# stepperDriver.net
KiCad netlist of a schematic drawn in EAGLE
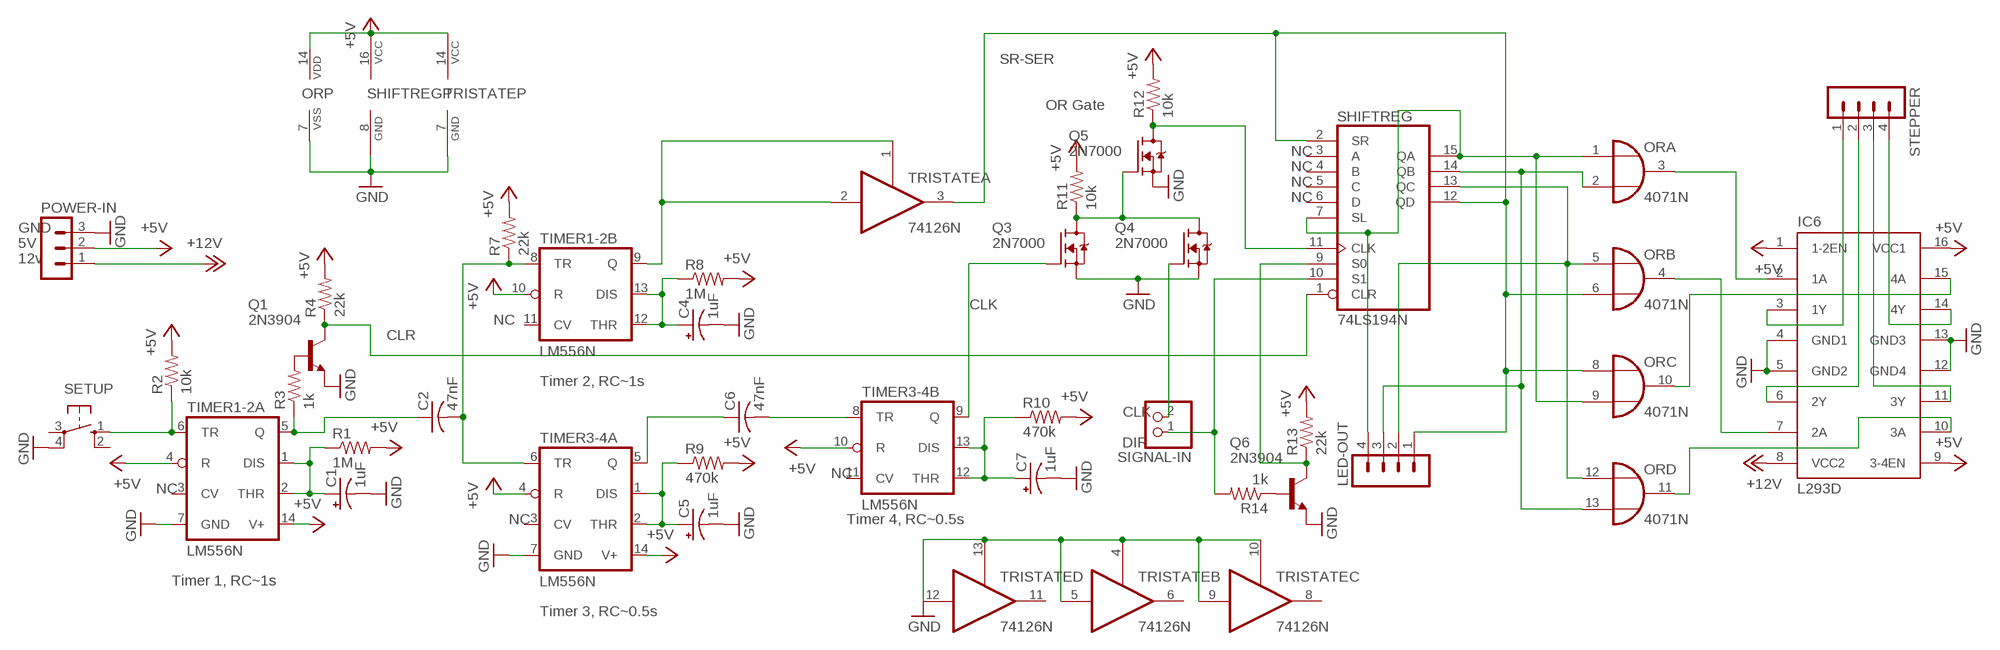
[diagram p0: schematic, sheet 1]

(export (version "E")
  (design (tool "Eeschema 10.0.6"))
  (components
    (comp (ref "C1")
      (value "1uF")
      (footprint "eagle-import:E2,5-6")
      (libsource (lib "eagle-import") (part "CPOL-USE2.5-6"))
    )
    (comp (ref "C2")
      (value "47nF")
      (footprint "eagle-import:C025-025X050")
      (libsource (lib "eagle-import") (part "C-US025-025X050"))
    )
    (comp (ref "C4")
      (value "1uF")
      (footprint "eagle-import:E2,5-6")
      (libsource (lib "eagle-import") (part "CPOL-USE2.5-6"))
    )
    (comp (ref "C5")
      (value "1uF")
      (footprint "eagle-import:E2,5-6")
      (libsource (lib "eagle-import") (part "CPOL-USE2.5-6"))
    )
    (comp (ref "C6")
      (value "47nF")
      (footprint "eagle-import:C025-025X050")
      (libsource (lib "eagle-import") (part "C-US025-025X050"))
    )
    (comp (ref "C7")
      (value "1uF")
      (footprint "eagle-import:E2,5-6")
      (libsource (lib "eagle-import") (part "CPOL-USE2.5-6"))
    )
    (comp (ref "IC6")
      (value "L293D")
      (footprint "eagle-import:DIL16")
      (libsource (lib "eagle-import") (part "L293D"))
    )
    (comp (ref "LED-OUT")
      (value "MA04-1")
      (footprint "eagle-import:MA04-1")
      (libsource (lib "eagle-import") (part "MA04-1"))
    )
    (comp (ref "OR")
      (value "4071N")
      (footprint "eagle-import:DIL14")
      (libsource (lib "eagle-import") (part "4071N"))
    )
    (comp (ref "POWER-IN")
      (value "MA03-1")
      (footprint "eagle-import:MA03-1")
      (libsource (lib "eagle-import") (part "MA03-1"))
    )
    (comp (ref "Q1")
      (value "2N3904")
      (footprint "eagle-import:TO92")
      (libsource (lib "eagle-import") (part "2N3904"))
    )
    (comp (ref "Q3")
      (value "2N7000")
      (footprint "eagle-import:TO92-")
      (libsource (lib "eagle-import") (part "2N7000"))
    )
    (comp (ref "Q4")
      (value "2N7000")
      (footprint "eagle-import:TO92-")
      (libsource (lib "eagle-import") (part "2N7000"))
    )
    (comp (ref "Q5")
      (value "2N7000")
      (footprint "eagle-import:TO92-")
      (libsource (lib "eagle-import") (part "2N7000"))
    )
    (comp (ref "Q6")
      (value "2N3904")
      (footprint "eagle-import:TO92")
      (libsource (lib "eagle-import") (part "2N3904"))
    )
    (comp (ref "R1")
      (value "1M")
      (footprint "eagle-import:0204_7")
      (libsource (lib "eagle-import") (part "R-US_0204/7"))
    )
    (comp (ref "R2")
      (value "10k")
      (footprint "eagle-import:0204_7")
      (libsource (lib "eagle-import") (part "R-US_0204/7"))
    )
    (comp (ref "R3")
      (value "1k")
      (footprint "eagle-import:0204_7")
      (libsource (lib "eagle-import") (part "R-US_0204/7"))
    )
    (comp (ref "R4")
      (value "22k")
      (footprint "eagle-import:0204_7")
      (libsource (lib "eagle-import") (part "R-US_0204/7"))
    )
    (comp (ref "R7")
      (value "22k")
      (footprint "eagle-import:0204_7")
      (libsource (lib "eagle-import") (part "R-US_0204/7"))
    )
    (comp (ref "R8")
      (value "1M")
      (footprint "eagle-import:0204_7")
      (libsource (lib "eagle-import") (part "R-US_0204/7"))
    )
    (comp (ref "R9")
      (value "470k")
      (footprint "eagle-import:0204_7")
      (libsource (lib "eagle-import") (part "R-US_0204/7"))
    )
    (comp (ref "R10")
      (value "470k")
      (footprint "eagle-import:0204_7")
      (libsource (lib "eagle-import") (part "R-US_0204/7"))
    )
    (comp (ref "R11")
      (value "10k")
      (footprint "eagle-import:0204_7")
      (libsource (lib "eagle-import") (part "R-US_0204/7"))
    )
    (comp (ref "R12")
      (value "10k")
      (footprint "eagle-import:0204_7")
      (libsource (lib "eagle-import") (part "R-US_0204/7"))
    )
    (comp (ref "R13")
      (value "22k")
      (footprint "eagle-import:0204_7")
      (libsource (lib "eagle-import") (part "R-US_0204/7"))
    )
    (comp (ref "R14")
      (value "1k")
      (footprint "eagle-import:0204_7")
      (libsource (lib "eagle-import") (part "R-US_0204/7"))
    )
    (comp (ref "SETUP")
      (value "10-XX")
      (footprint "eagle-import:B3F-10XX")
      (fields (field (name "MPN") "B3F-1000"))
      (libsource (lib "eagle-import") (part "10-XX"))
    )
    (comp (ref "SHIFTREG")
      (value "74LS194N")
      (footprint "eagle-import:DIL16")
      (libsource (lib "eagle-import") (part "74194NLS"))
    )
    (comp (ref "SIGNAL-IN")
      (value "PINHD-1X2")
      (footprint "eagle-import:1X02")
      (libsource (lib "eagle-import") (part "PINHD-1X2"))
    )
    (comp (ref "STEPPER")
      (value "MA04-1")
      (footprint "eagle-import:MA04-1")
      (libsource (lib "eagle-import") (part "MA04-1"))
    )
    (comp (ref "TIMER1-2")
      (value "LM556N")
      (footprint "eagle-import:DIL14")
      (libsource (lib "eagle-import") (part "556NLM"))
    )
    (comp (ref "TIMER3-4")
      (value "LM556N")
      (footprint "eagle-import:DIL14")
      (libsource (lib "eagle-import") (part "556NLM"))
    )
    (comp (ref "TRISTATE")
      (value "74126N")
      (footprint "eagle-import:DIL14")
      (libsource (lib "eagle-import") (part "74126N"))
    )
  )
  (nets
    (net (code "1") (name "+5V") (class "Default")
      (node (ref "IC6") (pin "1") (pinfunction "1-2EN_1") (pintype "input"))
      (node (ref "IC6") (pin "16") (pinfunction "VCC1_16") (pintype "power_in"))
      (node (ref "IC6") (pin "9") (pinfunction "3-4EN_9") (pintype "input"))
      (node (ref "OR") (pin "14") (pinfunction "VDD_14") (pintype "power_in"))
      (node (ref "POWER-IN") (pin "2") (pinfunction "2_2") (pintype "passive"))
      (node (ref "R1") (pin "2") (pinfunction "2_2") (pintype "passive"))
      (node (ref "R10") (pin "2") (pinfunction "2_2") (pintype "passive"))
      (node (ref "R11") (pin "2") (pinfunction "2_2") (pintype "passive"))
      (node (ref "R12") (pin "2") (pinfunction "2_2") (pintype "passive"))
      (node (ref "R13") (pin "2") (pinfunction "2_2") (pintype "passive"))
      (node (ref "R2") (pin "2") (pinfunction "2_2") (pintype "passive"))
      (node (ref "R4") (pin "2") (pinfunction "2_2") (pintype "passive"))
      (node (ref "R7") (pin "2") (pinfunction "2_2") (pintype "passive"))
      (node (ref "R8") (pin "2") (pinfunction "2_2") (pintype "passive"))
      (node (ref "R9") (pin "2") (pinfunction "2_2") (pintype "passive"))
      (node (ref "SHIFTREG") (pin "16") (pinfunction "VCC_16") (pintype "power_in"))
      (node (ref "TIMER1-2") (pin "10") (pinfunction "R_10") (pintype "input"))
      (node (ref "TIMER1-2") (pin "14") (pinfunction "V+_14") (pintype "power_in"))
      (node (ref "TIMER1-2") (pin "4") (pinfunction "R_4") (pintype "input"))
      (node (ref "TIMER3-4") (pin "10") (pinfunction "R_10") (pintype "input"))
      (node (ref "TIMER3-4") (pin "14") (pinfunction "V+_14") (pintype "power_in"))
      (node (ref "TIMER3-4") (pin "4") (pinfunction "R_4") (pintype "input"))
      (node (ref "TRISTATE") (pin "14") (pinfunction "VCC_14") (pintype "power_in"))
    )
    (net (code "2") (name "+12V") (class "Default")
      (node (ref "IC6") (pin "8") (pinfunction "VCC2_8") (pintype "power_in"))
      (node (ref "POWER-IN") (pin "1") (pinfunction "1_1") (pintype "passive"))
    )
    (net (code "3") (name "GND") (class "Default")
      (node (ref "C1") (pin "-") (pinfunction "-_-") (pintype "passive"))
      (node (ref "C4") (pin "-") (pinfunction "-_-") (pintype "passive"))
      (node (ref "C5") (pin "-") (pinfunction "-_-") (pintype "passive"))
      (node (ref "C7") (pin "-") (pinfunction "-_-") (pintype "passive"))
      (node (ref "IC6") (pin "12") (pinfunction "GND4_12") (pintype "power_in"))
      (node (ref "IC6") (pin "13") (pinfunction "GND3_13") (pintype "power_in"))
      (node (ref "IC6") (pin "4") (pinfunction "GND1_4") (pintype "power_in"))
      (node (ref "IC6") (pin "5") (pinfunction "GND2_5") (pintype "power_in"))
      (node (ref "OR") (pin "7") (pinfunction "VSS_7") (pintype "power_in"))
      (node (ref "POWER-IN") (pin "3") (pinfunction "3_3") (pintype "passive"))
      (node (ref "Q1") (pin "3") (pinfunction "E_3") (pintype "passive"))
      (node (ref "Q3") (pin "3") (pinfunction "S_3") (pintype "passive"))
      (node (ref "Q4") (pin "3") (pinfunction "S_3") (pintype "passive"))
      (node (ref "Q5") (pin "3") (pinfunction "S_3") (pintype "passive"))
      (node (ref "Q6") (pin "3") (pinfunction "E_3") (pintype "passive"))
      (node (ref "SETUP") (pin "4") (pinfunction "P1_4") (pintype "passive"))
      (node (ref "SHIFTREG") (pin "8") (pinfunction "GND_8") (pintype "power_in"))
      (node (ref "TIMER1-2") (pin "7") (pinfunction "GND_7") (pintype "power_in"))
      (node (ref "TIMER3-4") (pin "7") (pinfunction "GND_7") (pintype "power_in"))
      (node (ref "TRISTATE") (pin "10") (pinfunction "OE_10") (pintype "input"))
      (node (ref "TRISTATE") (pin "12") (pinfunction "I_12") (pintype "input"))
      (node (ref "TRISTATE") (pin "13") (pinfunction "OE_13") (pintype "input"))
      (node (ref "TRISTATE") (pin "4") (pinfunction "OE_4") (pintype "input"))
      (node (ref "TRISTATE") (pin "5") (pinfunction "I_5") (pintype "input"))
      (node (ref "TRISTATE") (pin "7") (pinfunction "GND_7") (pintype "power_in"))
      (node (ref "TRISTATE") (pin "9") (pinfunction "I_9") (pintype "input"))
    )
    (net (code "4") (name "Net-(IC6-1A)") (class "Default")
      (node (ref "IC6") (pin "2") (pinfunction "1A_2") (pintype "input"))
      (node (ref "OR") (pin "3") (pinfunction "O_3") (pintype "output"))
    )
    (net (code "5") (name "Net-(IC6-1Y)") (class "Default")
      (node (ref "IC6") (pin "3") (pinfunction "1Y_3") (pintype "output"))
      (node (ref "STEPPER") (pin "1") (pinfunction "1_1") (pintype "passive"))
    )
    (net (code "6") (name "Net-(IC6-2A)") (class "Default")
      (node (ref "IC6") (pin "7") (pinfunction "2A_7") (pintype "input"))
      (node (ref "OR") (pin "4") (pinfunction "O_4") (pintype "output"))
    )
    (net (code "7") (name "Net-(IC6-2Y)") (class "Default")
      (node (ref "IC6") (pin "6") (pinfunction "2Y_6") (pintype "output"))
      (node (ref "STEPPER") (pin "2") (pinfunction "2_2") (pintype "passive"))
    )
    (net (code "8") (name "Net-(IC6-3A)") (class "Default")
      (node (ref "IC6") (pin "10") (pinfunction "3A_10") (pintype "input"))
      (node (ref "OR") (pin "11") (pinfunction "O_11") (pintype "output"))
    )
    (net (code "9") (name "Net-(IC6-3Y)") (class "Default")
      (node (ref "IC6") (pin "11") (pinfunction "3Y_11") (pintype "output"))
      (node (ref "STEPPER") (pin "3") (pinfunction "3_3") (pintype "passive"))
    )
    (net (code "10") (name "Net-(IC6-4A)") (class "Default")
      (node (ref "IC6") (pin "15") (pinfunction "4A_15") (pintype "input"))
      (node (ref "OR") (pin "10") (pinfunction "O_10") (pintype "output"))
    )
    (net (code "11") (name "Net-(IC6-4Y)") (class "Default")
      (node (ref "IC6") (pin "14") (pinfunction "4Y_14") (pintype "output"))
      (node (ref "STEPPER") (pin "4") (pinfunction "4_4") (pintype "passive"))
    )
    (net (code "12") (name "Net-(ORA-I0)") (class "Default")
      (node (ref "LED-OUT") (pin "4") (pinfunction "4_4") (pintype "passive"))
      (node (ref "OR") (pin "1") (pinfunction "I0_1") (pintype "input"))
      (node (ref "OR") (pin "9") (pinfunction "I1_9") (pintype "input"))
      (node (ref "SHIFTREG") (pin "15") (pinfunction "QA_15") (pintype "output"))
      (node (ref "SHIFTREG") (pin "7") (pinfunction "SL_7") (pintype "input"))
    )
    (net (code "13") (name "Net-(ORA-I1)") (class "Default")
      (node (ref "LED-OUT") (pin "3") (pinfunction "3_3") (pintype "passive"))
      (node (ref "OR") (pin "13") (pinfunction "I1_13") (pintype "input"))
      (node (ref "OR") (pin "2") (pinfunction "I1_2") (pintype "input"))
      (node (ref "SHIFTREG") (pin "14") (pinfunction "QB_14") (pintype "output"))
    )
    (net (code "14") (name "Net-(ORB-I0)") (class "Default")
      (node (ref "LED-OUT") (pin "2") (pinfunction "2_2") (pintype "passive"))
      (node (ref "OR") (pin "12") (pinfunction "I0_12") (pintype "input"))
      (node (ref "OR") (pin "5") (pinfunction "I0_5") (pintype "input"))
      (node (ref "SHIFTREG") (pin "13") (pinfunction "QC_13") (pintype "output"))
    )
    (net (code "15") (name "Net-(ORB-I1)") (class "Default")
      (node (ref "LED-OUT") (pin "1") (pinfunction "1_1") (pintype "passive"))
      (node (ref "OR") (pin "6") (pinfunction "I1_6") (pintype "input"))
      (node (ref "OR") (pin "8") (pinfunction "I0_8") (pintype "input"))
      (node (ref "SHIFTREG") (pin "12") (pinfunction "QD_12") (pintype "output"))
      (node (ref "SHIFTREG") (pin "2") (pinfunction "SR_2") (pintype "input"))
      (node (ref "TRISTATE") (pin "3") (pinfunction "O_3") (pintype "output"))
    )
    (net (code "16") (name "Net-(Q1-B)") (class "Default")
      (node (ref "Q1") (pin "2") (pinfunction "B_2") (pintype "passive"))
      (node (ref "R3") (pin "2") (pinfunction "2_2") (pintype "passive"))
    )
    (net (code "17") (name "Net-(Q1-C)") (class "Default")
      (node (ref "Q1") (pin "1") (pinfunction "C_1") (pintype "passive"))
      (node (ref "R4") (pin "1") (pinfunction "1_1") (pintype "passive"))
      (node (ref "SHIFTREG") (pin "1") (pinfunction "CLR_1") (pintype "input"))
    )
    (net (code "18") (name "Net-(Q3-D)") (class "Default")
      (node (ref "Q3") (pin "1") (pinfunction "D_1") (pintype "passive"))
      (node (ref "Q4") (pin "1") (pinfunction "D_1") (pintype "passive"))
      (node (ref "Q5") (pin "2") (pinfunction "G_2") (pintype "passive"))
      (node (ref "R11") (pin "1") (pinfunction "1_1") (pintype "passive"))
    )
    (net (code "19") (name "Net-(Q3-G)") (class "Default")
      (node (ref "Q3") (pin "2") (pinfunction "G_2") (pintype "passive"))
      (node (ref "TIMER3-4") (pin "9") (pinfunction "Q_9") (pintype "output"))
    )
    (net (code "20") (name "Net-(Q4-G)") (class "Default")
      (node (ref "Q4") (pin "2") (pinfunction "G_2") (pintype "passive"))
      (node (ref "SIGNAL-IN") (pin "2") (pinfunction "2_2") (pintype "passive"))
    )
    (net (code "21") (name "Net-(Q5-D)") (class "Default")
      (node (ref "Q5") (pin "1") (pinfunction "D_1") (pintype "passive"))
      (node (ref "R12") (pin "1") (pinfunction "1_1") (pintype "passive"))
      (node (ref "SHIFTREG") (pin "11") (pinfunction "CLK_11") (pintype "input"))
    )
    (net (code "22") (name "Net-(Q6-B)") (class "Default")
      (node (ref "Q6") (pin "2") (pinfunction "B_2") (pintype "passive"))
      (node (ref "R14") (pin "1") (pinfunction "1_1") (pintype "passive"))
    )
    (net (code "23") (name "Net-(Q6-C)") (class "Default")
      (node (ref "Q6") (pin "1") (pinfunction "C_1") (pintype "passive"))
      (node (ref "R13") (pin "1") (pinfunction "1_1") (pintype "passive"))
      (node (ref "SHIFTREG") (pin "9") (pinfunction "S0_9") (pintype "input"))
    )
    (net (code "24") (name "Net-(SETUP-S)") (class "Default")
      (node (ref "R2") (pin "1") (pinfunction "1_1") (pintype "passive"))
      (node (ref "SETUP") (pin "1") (pinfunction "S_1") (pintype "passive"))
      (node (ref "TIMER1-2") (pin "6") (pinfunction "TR_6") (pintype "input"))
    )
    (net (code "25") (name "Net-(SHIFTREGA-S1)") (class "Default")
      (node (ref "R14") (pin "2") (pinfunction "2_2") (pintype "passive"))
      (node (ref "SHIFTREG") (pin "10") (pinfunction "S1_10") (pintype "input"))
      (node (ref "SIGNAL-IN") (pin "1") (pinfunction "1_1") (pintype "passive"))
    )
    (net (code "26") (name "Net-(TIMER1-2A-DIS)") (class "Default")
      (node (ref "C1") (pin "+") (pinfunction "+_+") (pintype "passive"))
      (node (ref "R1") (pin "1") (pinfunction "1_1") (pintype "passive"))
      (node (ref "TIMER1-2") (pin "1") (pinfunction "DIS_1") (pintype "input"))
      (node (ref "TIMER1-2") (pin "2") (pinfunction "THR_2") (pintype "input"))
    )
    (net (code "27") (name "Net-(TIMER1-2A-Q)") (class "Default")
      (node (ref "C2") (pin "1") (pinfunction "1_1") (pintype "passive"))
      (node (ref "R3") (pin "1") (pinfunction "1_1") (pintype "passive"))
      (node (ref "TIMER1-2") (pin "5") (pinfunction "Q_5") (pintype "output"))
    )
    (net (code "28") (name "Net-(TIMER1-2B-DIS)") (class "Default")
      (node (ref "C4") (pin "+") (pinfunction "+_+") (pintype "passive"))
      (node (ref "R8") (pin "1") (pinfunction "1_1") (pintype "passive"))
      (node (ref "TIMER1-2") (pin "12") (pinfunction "THR_12") (pintype "input"))
      (node (ref "TIMER1-2") (pin "13") (pinfunction "DIS_13") (pintype "input"))
    )
    (net (code "29") (name "Net-(TIMER1-2B-Q)") (class "Default")
      (node (ref "TIMER1-2") (pin "9") (pinfunction "Q_9") (pintype "output"))
      (node (ref "TRISTATE") (pin "1") (pinfunction "OE_1") (pintype "input"))
      (node (ref "TRISTATE") (pin "2") (pinfunction "I_2") (pintype "input"))
    )
    (net (code "30") (name "Net-(TIMER1-2B-TR)") (class "Default")
      (node (ref "C2") (pin "2") (pinfunction "2_2") (pintype "passive"))
      (node (ref "R7") (pin "1") (pinfunction "1_1") (pintype "passive"))
      (node (ref "TIMER1-2") (pin "8") (pinfunction "TR_8") (pintype "input"))
      (node (ref "TIMER3-4") (pin "6") (pinfunction "TR_6") (pintype "input"))
    )
    (net (code "31") (name "Net-(TIMER3-4A-DIS)") (class "Default")
      (node (ref "C5") (pin "+") (pinfunction "+_+") (pintype "passive"))
      (node (ref "R9") (pin "1") (pinfunction "1_1") (pintype "passive"))
      (node (ref "TIMER3-4") (pin "1") (pinfunction "DIS_1") (pintype "input"))
      (node (ref "TIMER3-4") (pin "2") (pinfunction "THR_2") (pintype "input"))
    )
    (net (code "32") (name "Net-(TIMER3-4A-Q)") (class "Default")
      (node (ref "C6") (pin "1") (pinfunction "1_1") (pintype "passive"))
      (node (ref "TIMER3-4") (pin "5") (pinfunction "Q_5") (pintype "output"))
    )
    (net (code "33") (name "Net-(TIMER3-4B-DIS)") (class "Default")
      (node (ref "C7") (pin "+") (pinfunction "+_+") (pintype "passive"))
      (node (ref "R10") (pin "1") (pinfunction "1_1") (pintype "passive"))
      (node (ref "TIMER3-4") (pin "12") (pinfunction "THR_12") (pintype "input"))
      (node (ref "TIMER3-4") (pin "13") (pinfunction "DIS_13") (pintype "input"))
    )
    (net (code "34") (name "Net-(TIMER3-4B-TR)") (class "Default")
      (node (ref "C6") (pin "2") (pinfunction "2_2") (pintype "passive"))
      (node (ref "TIMER3-4") (pin "8") (pinfunction "TR_8") (pintype "input"))
    )
    (net (code "35") (name "unconnected-(SETUP-P-Pad3)") (class "Default")
      (node (ref "SETUP") (pin "3") (pinfunction "P_3") (pintype "passive"))
    )
    (net (code "36") (name "unconnected-(SETUP-S1-Pad2)") (class "Default")
      (node (ref "SETUP") (pin "2") (pinfunction "S1_2") (pintype "passive"))
    )
    (net (code "37") (name "unconnected-(SHIFTREGA-A-Pad3)") (class "Default")
      (node (ref "SHIFTREG") (pin "3") (pinfunction "A_3") (pintype "input"))
    )
    (net (code "38") (name "unconnected-(SHIFTREGA-B-Pad4)") (class "Default")
      (node (ref "SHIFTREG") (pin "4") (pinfunction "B_4") (pintype "input"))
    )
    (net (code "39") (name "unconnected-(SHIFTREGA-C-Pad5)") (class "Default")
      (node (ref "SHIFTREG") (pin "5") (pinfunction "C_5") (pintype "input"))
    )
    (net (code "40") (name "unconnected-(SHIFTREGA-D-Pad6)") (class "Default")
      (node (ref "SHIFTREG") (pin "6") (pinfunction "D_6") (pintype "input"))
    )
    (net (code "41") (name "unconnected-(TIMER1-2A-CV-Pad3)") (class "Default")
      (node (ref "TIMER1-2") (pin "3") (pinfunction "CV_3") (pintype "input"))
    )
    (net (code "42") (name "unconnected-(TIMER1-2B-CV-Pad11)") (class "Default")
      (node (ref "TIMER1-2") (pin "11") (pinfunction "CV_11") (pintype "input"))
    )
    (net (code "43") (name "unconnected-(TIMER3-4A-CV-Pad3)") (class "Default")
      (node (ref "TIMER3-4") (pin "3") (pinfunction "CV_3") (pintype "input"))
    )
    (net (code "44") (name "unconnected-(TIMER3-4B-CV-Pad11)") (class "Default")
      (node (ref "TIMER3-4") (pin "11") (pinfunction "CV_11") (pintype "input"))
    )
    (net (code "45") (name "unconnected-(TRISTATEB-O-Pad6)") (class "Default")
      (node (ref "TRISTATE") (pin "6") (pinfunction "O_6") (pintype "output"))
    )
    (net (code "46") (name "unconnected-(TRISTATEC-O-Pad8)") (class "Default")
      (node (ref "TRISTATE") (pin "8") (pinfunction "O_8") (pintype "output"))
    )
    (net (code "47") (name "unconnected-(TRISTATED-O-Pad11)") (class "Default")
      (node (ref "TRISTATE") (pin "11") (pinfunction "O_11") (pintype "output"))
    )
  )
)
